# sch_Camera.net
KiCad netlist of a schematic drawn in Altium Designer
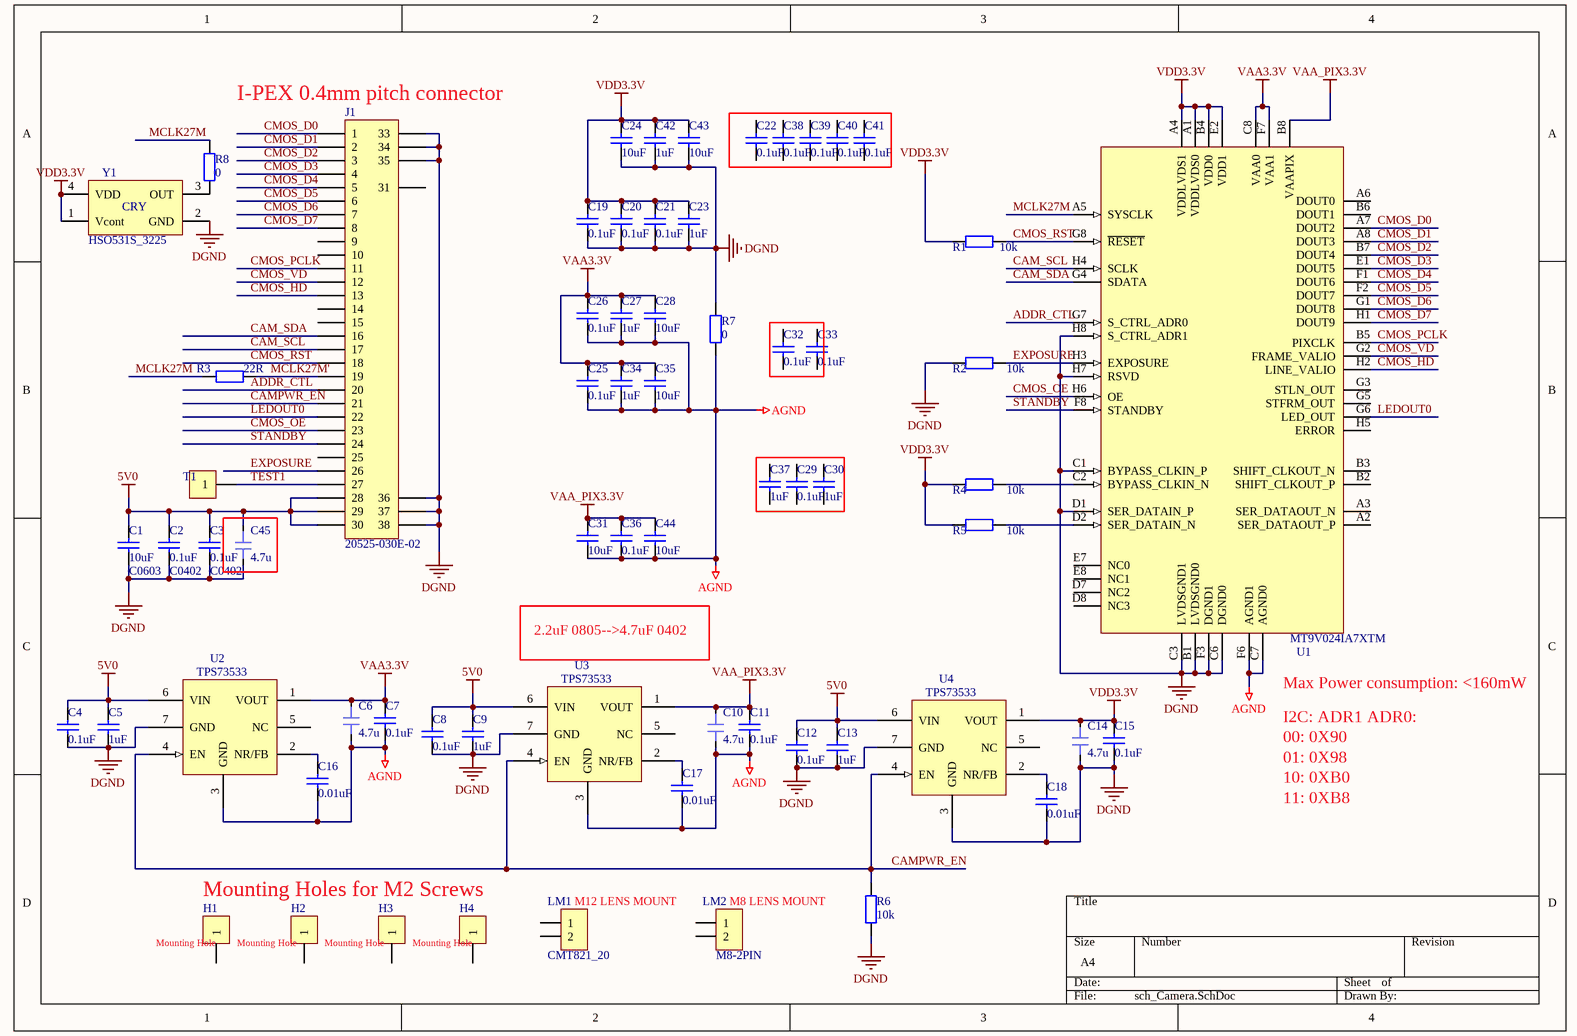
[diagram p0: sch_Camera.SchDoc]

(export (version "E")
  (design (tool "Eeschema 10.0.6"))
  (components
    (comp (ref "C1")
      (value "10uF")
      (footprint "0805C")
      (description "Capacitor")
      (fields (field (name "ALTIUM_VALUE") "C0603") (field (name "PUBLISHER") "Altium Limited"))
      (libsource (lib "Miscellaneous Devices") (part "Cap"))
    )
    (comp (ref "C2")
      (value "0.1uF")
      (footprint "0402C")
      (description "Capacitor")
      (fields (field (name "ALTIUM_VALUE") "C0402") (field (name "PUBLISHER") "Altium Limited"))
      (libsource (lib "Miscellaneous Devices") (part "Cap"))
    )
    (comp (ref "C3")
      (value "0.1uF")
      (footprint "0402C")
      (description "Capacitor")
      (fields (field (name "ALTIUM_VALUE") "C0402") (field (name "PUBLISHER") "Altium Limited"))
      (libsource (lib "Miscellaneous Devices") (part "Cap"))
    )
    (comp (ref "C4")
      (value "0.1uF")
      (footprint "0402C")
      (description "Capacitor")
      (fields (field (name "PUBLISHER") "Altium Limited"))
      (libsource (lib "Miscellaneous Devices") (part "Cap"))
    )
    (comp (ref "C5")
      (value "1uF")
      (footprint "0402C")
      (description "Capacitor")
      (fields (field (name "PUBLISHER") "Altium Limited"))
      (libsource (lib "Miscellaneous Devices") (part "Cap"))
    )
    (comp (ref "C6")
      (value "4.7u")
      (footprint "0402C")
      (description "CC0402MRX5R5BB475")
      (libsource (lib "V0P1") (part "cap0402"))
    )
    (comp (ref "C7")
      (value "0.1uF")
      (footprint "0402C")
      (description "Capacitor")
      (fields (field (name "PUBLISHER") "Altium Limited"))
      (libsource (lib "Miscellaneous Devices") (part "Cap"))
    )
    (comp (ref "C8")
      (value "0.1uF")
      (footprint "0402C")
      (description "Capacitor")
      (fields (field (name "PUBLISHER") "Altium Limited"))
      (libsource (lib "Miscellaneous Devices") (part "Cap"))
    )
    (comp (ref "C9")
      (value "1uF")
      (footprint "0402C")
      (description "Capacitor")
      (fields (field (name "PUBLISHER") "Altium Limited"))
      (libsource (lib "Miscellaneous Devices") (part "Cap"))
    )
    (comp (ref "C10")
      (value "4.7u")
      (footprint "0402C")
      (description "CC0402MRX5R5BB475")
      (libsource (lib "V0P1") (part "cap0402"))
    )
    (comp (ref "C11")
      (value "0.1uF")
      (footprint "0402C")
      (description "Capacitor")
      (fields (field (name "PUBLISHER") "Altium Limited"))
      (libsource (lib "Miscellaneous Devices") (part "Cap"))
    )
    (comp (ref "C12")
      (value "0.1uF")
      (footprint "0402C")
      (description "Capacitor")
      (fields (field (name "PUBLISHER") "Altium Limited"))
      (libsource (lib "Miscellaneous Devices") (part "Cap"))
    )
    (comp (ref "C13")
      (value "1uF")
      (footprint "0402C")
      (description "Capacitor")
      (fields (field (name "PUBLISHER") "Altium Limited"))
      (libsource (lib "Miscellaneous Devices") (part "Cap"))
    )
    (comp (ref "C14")
      (value "4.7u")
      (footprint "0402C")
      (description "CC0402MRX5R5BB475")
      (libsource (lib "V0P1") (part "cap0402"))
    )
    (comp (ref "C15")
      (value "0.1uF")
      (footprint "0402C")
      (description "Capacitor")
      (fields (field (name "PUBLISHER") "Altium Limited"))
      (libsource (lib "Miscellaneous Devices") (part "Cap"))
    )
    (comp (ref "C16")
      (value "0.01uF")
      (footprint "0402C")
      (description "Capacitor")
      (fields (field (name "PUBLISHER") "Altium Limited"))
      (libsource (lib "Miscellaneous Devices") (part "Cap"))
    )
    (comp (ref "C17")
      (value "0.01uF")
      (footprint "0402C")
      (description "Capacitor")
      (fields (field (name "PUBLISHER") "Altium Limited"))
      (libsource (lib "Miscellaneous Devices") (part "Cap"))
    )
    (comp (ref "C18")
      (value "0.01uF")
      (footprint "0402C")
      (description "Capacitor")
      (fields (field (name "PUBLISHER") "Altium Limited"))
      (libsource (lib "Miscellaneous Devices") (part "Cap"))
    )
    (comp (ref "C19")
      (value "0.1uF")
      (footprint "0402C")
      (description "Capacitor")
      (fields (field (name "PUBLISHER") "Altium Limited"))
      (libsource (lib "Miscellaneous Devices") (part "Cap"))
    )
    (comp (ref "C20")
      (value "0.1uF")
      (footprint "0402C")
      (description "Capacitor")
      (fields (field (name "PUBLISHER") "Altium Limited"))
      (libsource (lib "Miscellaneous Devices") (part "Cap"))
    )
    (comp (ref "C21")
      (value "0.1uF")
      (footprint "0402C")
      (description "Capacitor")
      (fields (field (name "PUBLISHER") "Altium Limited"))
      (libsource (lib "Miscellaneous Devices") (part "Cap"))
    )
    (comp (ref "C22")
      (value "0.1uF")
      (footprint "0402C")
      (description "Capacitor")
      (fields (field (name "PUBLISHER") "Altium Limited"))
      (libsource (lib "Miscellaneous Devices") (part "Cap"))
    )
    (comp (ref "C23")
      (value "1uF")
      (footprint "0402C")
      (description "Capacitor")
      (fields (field (name "PUBLISHER") "Altium Limited"))
      (libsource (lib "Miscellaneous Devices") (part "Cap"))
    )
    (comp (ref "C24")
      (value "10uF")
      (footprint "0805C")
      (description "Capacitor")
      (fields (field (name "PUBLISHER") "Altium Limited"))
      (libsource (lib "Miscellaneous Devices") (part "Cap"))
    )
    (comp (ref "C25")
      (value "0.1uF")
      (footprint "0402C")
      (description "Capacitor")
      (fields (field (name "PUBLISHER") "Altium Limited"))
      (libsource (lib "Miscellaneous Devices") (part "Cap"))
    )
    (comp (ref "C26")
      (value "0.1uF")
      (footprint "0402C")
      (description "Capacitor")
      (fields (field (name "PUBLISHER") "Altium Limited"))
      (libsource (lib "Miscellaneous Devices") (part "Cap"))
    )
    (comp (ref "C27")
      (value "1uF")
      (footprint "0402C")
      (description "Capacitor")
      (fields (field (name "PUBLISHER") "Altium Limited"))
      (libsource (lib "Miscellaneous Devices") (part "Cap"))
    )
    (comp (ref "C28")
      (value "10uF")
      (footprint "0805C")
      (description "Capacitor")
      (fields (field (name "PUBLISHER") "Altium Limited"))
      (libsource (lib "Miscellaneous Devices") (part "Cap"))
    )
    (comp (ref "C29")
      (value "0.1uF")
      (footprint "0402C")
      (description "Capacitor")
      (fields (field (name "PUBLISHER") "Altium Limited"))
      (libsource (lib "Miscellaneous Devices") (part "Cap"))
    )
    (comp (ref "C30")
      (value "1uF")
      (footprint "0402C")
      (description "Capacitor")
      (fields (field (name "PUBLISHER") "Altium Limited"))
      (libsource (lib "Miscellaneous Devices") (part "Cap"))
    )
    (comp (ref "C31")
      (value "10uF")
      (footprint "0805C")
      (description "Capacitor")
      (fields (field (name "PUBLISHER") "Altium Limited"))
      (libsource (lib "Miscellaneous Devices") (part "Cap"))
    )
    (comp (ref "C32")
      (value "0.1uF")
      (footprint "0402C")
      (description "Capacitor")
      (fields (field (name "PUBLISHER") "Altium Limited"))
      (libsource (lib "Miscellaneous Devices") (part "Cap"))
    )
    (comp (ref "C33")
      (value "0.1uF")
      (footprint "0402C")
      (description "Capacitor")
      (fields (field (name "PUBLISHER") "Altium Limited"))
      (libsource (lib "Miscellaneous Devices") (part "Cap"))
    )
    (comp (ref "C34")
      (value "1uF")
      (footprint "0402C")
      (description "Capacitor")
      (fields (field (name "PUBLISHER") "Altium Limited"))
      (libsource (lib "Miscellaneous Devices") (part "Cap"))
    )
    (comp (ref "C35")
      (value "10uF")
      (footprint "0805C")
      (description "Capacitor")
      (fields (field (name "PUBLISHER") "Altium Limited"))
      (libsource (lib "Miscellaneous Devices") (part "Cap"))
    )
    (comp (ref "C36")
      (value "0.1uF")
      (footprint "0402C")
      (description "Capacitor")
      (fields (field (name "PUBLISHER") "Altium Limited"))
      (libsource (lib "Miscellaneous Devices") (part "Cap"))
    )
    (comp (ref "C37")
      (value "1uF")
      (footprint "0402C")
      (description "Capacitor")
      (fields (field (name "PUBLISHER") "Altium Limited"))
      (libsource (lib "Miscellaneous Devices") (part "Cap"))
    )
    (comp (ref "C38")
      (value "0.1uF")
      (footprint "0402C")
      (description "Capacitor")
      (fields (field (name "PUBLISHER") "Altium Limited"))
      (libsource (lib "Miscellaneous Devices") (part "Cap"))
    )
    (comp (ref "C39")
      (value "0.1uF")
      (footprint "0402C")
      (description "Capacitor")
      (fields (field (name "PUBLISHER") "Altium Limited"))
      (libsource (lib "Miscellaneous Devices") (part "Cap"))
    )
    (comp (ref "C40")
      (value "0.1uF")
      (footprint "0402C")
      (description "Capacitor")
      (fields (field (name "PUBLISHER") "Altium Limited"))
      (libsource (lib "Miscellaneous Devices") (part "Cap"))
    )
    (comp (ref "C41")
      (value "0.1uF")
      (footprint "0402C")
      (description "Capacitor")
      (fields (field (name "PUBLISHER") "Altium Limited"))
      (libsource (lib "Miscellaneous Devices") (part "Cap"))
    )
    (comp (ref "C42")
      (value "1uF")
      (footprint "0402C")
      (description "Capacitor")
      (fields (field (name "PUBLISHER") "Altium Limited"))
      (libsource (lib "Miscellaneous Devices") (part "Cap"))
    )
    (comp (ref "C43")
      (value "10uF")
      (footprint "0805C")
      (description "Capacitor")
      (fields (field (name "PUBLISHER") "Altium Limited"))
      (libsource (lib "Miscellaneous Devices") (part "Cap"))
    )
    (comp (ref "C44")
      (value "10uF")
      (footprint "0805C")
      (description "Capacitor")
      (fields (field (name "PUBLISHER") "Altium Limited"))
      (libsource (lib "Miscellaneous Devices") (part "Cap"))
    )
    (comp (ref "C45")
      (value "4.7u")
      (footprint "0402C")
      (description "CC0402MRX5R5BB475")
      (libsource (lib "V0P1") (part "cap0402"))
    )
    (comp (ref "H1")
      (value "CON1")
      (footprint "PAD_M3_D350_450")
      (description "Connector")
      (libsource (lib "") (part "CON1_1"))
    )
    (comp (ref "H2")
      (value "CON1")
      (footprint "PAD_M3_D350_450")
      (description "Connector")
      (libsource (lib "") (part "CON1_1"))
    )
    (comp (ref "H3")
      (value "CON1")
      (footprint "PAD_M3_D350_450")
      (description "Connector")
      (libsource (lib "") (part "CON1_1"))
    )
    (comp (ref "H4")
      (value "CON1")
      (footprint "PAD_M3_D350_450")
      (description "Connector")
      (libsource (lib "") (part "CON1_1"))
    )
    (comp (ref "J1")
      (value "20525-030E-02")
      (footprint "HSA30_P40L196W42H10_20525")
      (libsource (lib "SZG") (part "20525-030E-02"))
    )
    (comp (ref "LM1")
      (value "CMT821_20")
      (footprint "PAD_M3_D350_450")
      (description "Connector")
      (libsource (lib "SuperSchLib") (part "CON2"))
    )
    (comp (ref "LM2")
      (value "M8-2PIN")
      (footprint "PAD_M3_D350_450")
      (description "Connector")
      (libsource (lib "SuperSchLib") (part "CON2"))
    )
    (comp (ref "R1")
      (value "10k")
      (footprint "0402R")
      (description "Resistor")
      (fields (field (name "Comment") "10K") (field (name "PUBLISHER") "Altium Limited"))
      (libsource (lib "SZG") (part "Resistor"))
    )
    (comp (ref "R2")
      (value "10k")
      (footprint "0402R")
      (description "Resistor")
      (fields (field (name "Comment") "10K") (field (name "PUBLISHER") "Altium Limited"))
      (libsource (lib "SZG") (part "Resistor"))
    )
    (comp (ref "R3")
      (value "22R")
      (footprint "0402R")
      (description "Resistor")
      (fields (field (name "PUBLISHER") "Altium Limited"))
      (libsource (lib "") (part "Resistor_2"))
    )
    (comp (ref "R4")
      (value "10k")
      (footprint "0402R")
      (description "Resistor")
      (fields (field (name "Comment") "10K") (field (name "PUBLISHER") "Altium Limited"))
      (libsource (lib "SZG") (part "Resistor"))
    )
    (comp (ref "R5")
      (value "10k")
      (footprint "0402R")
      (description "Resistor")
      (fields (field (name "Comment") "10K") (field (name "PUBLISHER") "Altium Limited"))
      (libsource (lib "SZG") (part "Resistor"))
    )
    (comp (ref "R6")
      (value "10k")
      (footprint "0402R")
      (description "Resistor")
      (fields (field (name "Comment") "10K") (field (name "PUBLISHER") "Altium Limited"))
      (libsource (lib "") (part "Resistor_3"))
    )
    (comp (ref "R7")
      (value "0")
      (footprint "0402R")
      (description "Resistor")
      (fields (field (name "Comment") "0R") (field (name "PUBLISHER") "Altium Limited"))
      (libsource (lib "") (part "Resistor_1"))
    )
    (comp (ref "R8")
      (value "0")
      (footprint "0402R")
      (description "Resistor")
      (fields (field (name "Comment") "0R") (field (name "PUBLISHER") "Altium Limited"))
      (libsource (lib "") (part "Resistor_1"))
    )
    (comp (ref "T1")
      (value "CON1")
      (footprint "PAD_TP_D1.2")
      (description "Connector")
      (libsource (lib "SuperSchLib") (part "CON1"))
    )
    (comp (ref "U1")
      (value "MT9V024IA7XTM")
      (footprint "IBGA52_8X8_P100L90W90H90R")
      (libsource (lib "SZG") (part "MT9V024IA7XTM"))
    )
    (comp (ref "U2")
      (value "TPS73533")
      (footprint "QFN8_P65L30W30H10_DRB")
      (libsource (lib "SZG") (part "TPS73533"))
    )
    (comp (ref "U3")
      (value "TPS73533")
      (footprint "QFN8_P65L30W30H10_DRB")
      (libsource (lib "SZG") (part "TPS73533"))
    )
    (comp (ref "U4")
      (value "TPS73533")
      (footprint "QFN8_P65L30W30H10_DRB")
      (libsource (lib "SZG") (part "TPS73533"))
    )
    (comp (ref "Y1")
      (value "HSO531S_3225")
      (footprint "XTAL_3225")
      (description "有源晶振")
      (libsource (lib "超集元件库") (part "CRY"))
    )
  )
  (nets
    (net (code "1") (name "/ADDR_CTL") (class "Default")
      (node (ref "J1") (pin "20") (pinfunction "20_20") (pintype "passive"))
      (node (ref "U1") (pin "G7") (pinfunction "S_CTRL_ADR0_G7") (pintype "input"))
    )
    (net (code "2") (name "/CAMPWR_EN") (class "Default")
      (node (ref "J1") (pin "21") (pinfunction "21_21") (pintype "passive"))
      (node (ref "R6") (pin "2") (pinfunction "2_2") (pintype "passive"))
      (node (ref "U2") (pin "4") (pinfunction "EN_4") (pintype "input"))
      (node (ref "U3") (pin "4") (pinfunction "EN_4") (pintype "input"))
      (node (ref "U4") (pin "4") (pinfunction "EN_4") (pintype "input"))
    )
    (net (code "3") (name "/CAM_SCL") (class "Default")
      (node (ref "J1") (pin "17") (pinfunction "17_17") (pintype "passive"))
      (node (ref "U1") (pin "H4") (pinfunction "SCLK_H4") (pintype "input"))
    )
    (net (code "4") (name "/CAM_SDA") (class "Default")
      (node (ref "J1") (pin "16") (pinfunction "16_16") (pintype "passive"))
      (node (ref "U1") (pin "G4") (pinfunction "SDATA_G4") (pintype "passive"))
    )
    (net (code "5") (name "/CMOS_D0") (class "Default")
      (node (ref "J1") (pin "1") (pinfunction "1_1") (pintype "passive"))
      (node (ref "U1") (pin "A7") (pinfunction "DOUT2_A7") (pintype "passive"))
    )
    (net (code "6") (name "/CMOS_D1") (class "Default")
      (node (ref "J1") (pin "2") (pinfunction "2_2") (pintype "passive"))
      (node (ref "U1") (pin "A8") (pinfunction "DOUT3_A8") (pintype "passive"))
    )
    (net (code "7") (name "/CMOS_D2") (class "Default")
      (node (ref "J1") (pin "3") (pinfunction "3_3") (pintype "passive"))
      (node (ref "U1") (pin "B7") (pinfunction "DOUT4_B7") (pintype "passive"))
    )
    (net (code "8") (name "/CMOS_D3") (class "Default")
      (node (ref "J1") (pin "4") (pinfunction "4_4") (pintype "passive"))
      (node (ref "U1") (pin "E1") (pinfunction "DOUT5_E1") (pintype "passive"))
    )
    (net (code "9") (name "/CMOS_D4") (class "Default")
      (node (ref "J1") (pin "5") (pinfunction "5_5") (pintype "passive"))
      (node (ref "U1") (pin "F1") (pinfunction "DOUT6_F1") (pintype "passive"))
    )
    (net (code "10") (name "/CMOS_D5") (class "Default")
      (node (ref "J1") (pin "6") (pinfunction "6_6") (pintype "passive"))
      (node (ref "U1") (pin "F2") (pinfunction "DOUT7_F2") (pintype "passive"))
    )
    (net (code "11") (name "/CMOS_D6") (class "Default")
      (node (ref "J1") (pin "7") (pinfunction "7_7") (pintype "passive"))
      (node (ref "U1") (pin "G1") (pinfunction "DOUT8_G1") (pintype "passive"))
    )
    (net (code "12") (name "/CMOS_D7") (class "Default")
      (node (ref "J1") (pin "8") (pinfunction "8_8") (pintype "passive"))
      (node (ref "U1") (pin "H1") (pinfunction "DOUT9_H1") (pintype "passive"))
    )
    (net (code "13") (name "/CMOS_HD") (class "Default")
      (node (ref "J1") (pin "13") (pinfunction "13_13") (pintype "passive"))
      (node (ref "U1") (pin "H2") (pinfunction "LINE_VALIO_H2") (pintype "passive"))
    )
    (net (code "14") (name "/CMOS_OE") (class "Default")
      (node (ref "J1") (pin "23") (pinfunction "23_23") (pintype "passive"))
      (node (ref "U1") (pin "H6") (pinfunction "OE_H6") (pintype "input"))
    )
    (net (code "15") (name "/CMOS_PCLK") (class "Default")
      (node (ref "J1") (pin "11") (pinfunction "11_11") (pintype "passive"))
      (node (ref "U1") (pin "B5") (pinfunction "PIXCLK_B5") (pintype "passive"))
    )
    (net (code "16") (name "/CMOS_RST") (class "Default")
      (node (ref "J1") (pin "18") (pinfunction "18_18") (pintype "passive"))
      (node (ref "R1") (pin "1") (pinfunction "1_1") (pintype "passive"))
      (node (ref "U1") (pin "G8") (pinfunction "~{RESET}_G8") (pintype "input"))
    )
    (net (code "17") (name "/CMOS_VD") (class "Default")
      (node (ref "J1") (pin "12") (pinfunction "12_12") (pintype "passive"))
      (node (ref "U1") (pin "G2") (pinfunction "FRAME_VALIO_G2") (pintype "passive"))
    )
    (net (code "18") (name "/EXPOSURE") (class "Default")
      (node (ref "J1") (pin "26") (pinfunction "26_26") (pintype "passive"))
      (node (ref "R2") (pin "1") (pinfunction "1_1") (pintype "passive"))
      (node (ref "U1") (pin "H3") (pinfunction "EXPOSURE_H3") (pintype "input"))
    )
    (net (code "19") (name "/LEDOUT0") (class "Default")
      (node (ref "J1") (pin "22") (pinfunction "22_22") (pintype "passive"))
      (node (ref "U1") (pin "G6") (pinfunction "LED_OUT_G6") (pintype "passive"))
    )
    (net (code "20") (name "/MCLK27M") (class "Default")
      (node (ref "R3") (pin "1") (pinfunction "1_1") (pintype "passive"))
      (node (ref "R8") (pin "1") (pinfunction "1_1") (pintype "passive"))
      (node (ref "U1") (pin "A5") (pinfunction "SYSCLK_A5") (pintype "input"))
    )
    (net (code "21") (name "/MCLK27M'") (class "Default")
      (node (ref "J1") (pin "19") (pinfunction "19_19") (pintype "passive"))
      (node (ref "R3") (pin "2") (pinfunction "2_2") (pintype "passive"))
    )
    (net (code "22") (name "/STANDBY") (class "Default")
      (node (ref "J1") (pin "24") (pinfunction "24_24") (pintype "passive"))
      (node (ref "U1") (pin "F8") (pinfunction "STANDBY_F8") (pintype "input"))
    )
    (net (code "23") (name "/TEST1") (class "Default")
      (node (ref "J1") (pin "27") (pinfunction "27_27") (pintype "passive"))
      (node (ref "T1") (pin "1") (pinfunction "1_1") (pintype "passive"))
    )
    (net (code "24") (name "5V0") (class "Default")
      (node (ref "C1") (pin "2") (pinfunction "2_2") (pintype "passive"))
      (node (ref "C12") (pin "2") (pinfunction "2_2") (pintype "passive"))
      (node (ref "C13") (pin "2") (pinfunction "2_2") (pintype "passive"))
      (node (ref "C2") (pin "2") (pinfunction "2_2") (pintype "passive"))
      (node (ref "C3") (pin "2") (pinfunction "2_2") (pintype "passive"))
      (node (ref "C4") (pin "2") (pinfunction "2_2") (pintype "passive"))
      (node (ref "C45") (pin "1") (pinfunction "1_1") (pintype "passive"))
      (node (ref "C5") (pin "2") (pinfunction "2_2") (pintype "passive"))
      (node (ref "C8") (pin "2") (pinfunction "2_2") (pintype "passive"))
      (node (ref "C9") (pin "2") (pinfunction "2_2") (pintype "passive"))
      (node (ref "J1") (pin "28") (pinfunction "28_28") (pintype "passive"))
      (node (ref "J1") (pin "29") (pinfunction "29_29") (pintype "passive"))
      (node (ref "J1") (pin "30") (pinfunction "30_30") (pintype "passive"))
      (node (ref "U2") (pin "6") (pinfunction "VIN_6") (pintype "passive"))
      (node (ref "U3") (pin "6") (pinfunction "VIN_6") (pintype "passive"))
      (node (ref "U4") (pin "6") (pinfunction "VIN_6") (pintype "passive"))
    )
    (net (code "25") (name "AGND") (class "Default")
      (node (ref "C10") (pin "2") (pinfunction "2_2") (pintype "passive"))
      (node (ref "C11") (pin "1") (pinfunction "1_1") (pintype "passive"))
      (node (ref "C16") (pin "1") (pinfunction "1_1") (pintype "passive"))
      (node (ref "C17") (pin "1") (pinfunction "1_1") (pintype "passive"))
      (node (ref "C25") (pin "1") (pinfunction "1_1") (pintype "passive"))
      (node (ref "C26") (pin "1") (pinfunction "1_1") (pintype "passive"))
      (node (ref "C27") (pin "1") (pinfunction "1_1") (pintype "passive"))
      (node (ref "C28") (pin "1") (pinfunction "1_1") (pintype "passive"))
      (node (ref "C31") (pin "1") (pinfunction "1_1") (pintype "passive"))
      (node (ref "C34") (pin "1") (pinfunction "1_1") (pintype "passive"))
      (node (ref "C35") (pin "1") (pinfunction "1_1") (pintype "passive"))
      (node (ref "C36") (pin "1") (pinfunction "1_1") (pintype "passive"))
      (node (ref "C44") (pin "1") (pinfunction "1_1") (pintype "passive"))
      (node (ref "C6") (pin "2") (pinfunction "2_2") (pintype "passive"))
      (node (ref "C7") (pin "1") (pinfunction "1_1") (pintype "passive"))
      (node (ref "R7") (pin "2") (pinfunction "2_2") (pintype "passive"))
      (node (ref "U1") (pin "C7") (pinfunction "AGND0_C7") (pintype "power_in"))
      (node (ref "U1") (pin "F6") (pinfunction "AGND1_F6") (pintype "power_in"))
      (node (ref "U2") (pin "3") (pinfunction "GND_3") (pintype "passive"))
      (node (ref "U3") (pin "3") (pinfunction "GND_3") (pintype "passive"))
    )
    (net (code "26") (name "DGND") (class "Default")
      (node (ref "C1") (pin "1") (pinfunction "1_1") (pintype "passive"))
      (node (ref "C12") (pin "1") (pinfunction "1_1") (pintype "passive"))
      (node (ref "C13") (pin "1") (pinfunction "1_1") (pintype "passive"))
      (node (ref "C14") (pin "2") (pinfunction "2_2") (pintype "passive"))
      (node (ref "C15") (pin "1") (pinfunction "1_1") (pintype "passive"))
      (node (ref "C18") (pin "1") (pinfunction "1_1") (pintype "passive"))
      (node (ref "C19") (pin "1") (pinfunction "1_1") (pintype "passive"))
      (node (ref "C2") (pin "1") (pinfunction "1_1") (pintype "passive"))
      (node (ref "C20") (pin "1") (pinfunction "1_1") (pintype "passive"))
      (node (ref "C21") (pin "1") (pinfunction "1_1") (pintype "passive"))
      (node (ref "C23") (pin "1") (pinfunction "1_1") (pintype "passive"))
      (node (ref "C24") (pin "1") (pinfunction "1_1") (pintype "passive"))
      (node (ref "C3") (pin "1") (pinfunction "1_1") (pintype "passive"))
      (node (ref "C4") (pin "1") (pinfunction "1_1") (pintype "passive"))
      (node (ref "C42") (pin "1") (pinfunction "1_1") (pintype "passive"))
      (node (ref "C43") (pin "1") (pinfunction "1_1") (pintype "passive"))
      (node (ref "C45") (pin "2") (pinfunction "2_2") (pintype "passive"))
      (node (ref "C5") (pin "1") (pinfunction "1_1") (pintype "passive"))
      (node (ref "C8") (pin "1") (pinfunction "1_1") (pintype "passive"))
      (node (ref "C9") (pin "1") (pinfunction "1_1") (pintype "passive"))
      (node (ref "J1") (pin "33") (pinfunction "33_33") (pintype "passive"))
      (node (ref "J1") (pin "34") (pinfunction "34_34") (pintype "passive"))
      (node (ref "J1") (pin "35") (pinfunction "35_35") (pintype "passive"))
      (node (ref "J1") (pin "36") (pinfunction "36_36") (pintype "passive"))
      (node (ref "J1") (pin "37") (pinfunction "37_37") (pintype "passive"))
      (node (ref "J1") (pin "38") (pinfunction "38_38") (pintype "passive"))
      (node (ref "R2") (pin "2") (pinfunction "2_2") (pintype "passive"))
      (node (ref "R6") (pin "1") (pinfunction "1_1") (pintype "passive"))
      (node (ref "R7") (pin "1") (pinfunction "1_1") (pintype "passive"))
      (node (ref "U1") (pin "B1") (pinfunction "LVDSGND0_B1") (pintype "power_in"))
      (node (ref "U1") (pin "C1") (pinfunction "BYPASS_CLKIN_P_C1") (pintype "input"))
      (node (ref "U1") (pin "C3") (pinfunction "LVDSGND1_C3") (pintype "power_in"))
      (node (ref "U1") (pin "C6") (pinfunction "DGND0_C6") (pintype "power_in"))
      (node (ref "U1") (pin "D1") (pinfunction "SER_DATAIN_P_D1") (pintype "input"))
      (node (ref "U1") (pin "F3") (pinfunction "DGND1_F3") (pintype "power_in"))
      (node (ref "U1") (pin "H7") (pinfunction "RSVD_H7") (pintype "input"))
      (node (ref "U1") (pin "H8") (pinfunction "S_CTRL_ADR1_H8") (pintype "input"))
      (node (ref "U2") (pin "7") (pinfunction "GND_7") (pintype "passive"))
      (node (ref "U3") (pin "7") (pinfunction "GND_7") (pintype "passive"))
      (node (ref "U4") (pin "3") (pinfunction "GND_3") (pintype "passive"))
      (node (ref "U4") (pin "7") (pinfunction "GND_7") (pintype "passive"))
      (node (ref "Y1") (pin "2") (pinfunction "GND_2") (pintype "passive"))
    )
    (net (code "27") (name "Net-(U1-BYPASS_CLKIN_N)") (class "Default")
      (node (ref "R4") (pin "1") (pinfunction "1_1") (pintype "passive"))
      (node (ref "U1") (pin "C2") (pinfunction "BYPASS_CLKIN_N_C2") (pintype "input"))
    )
    (net (code "28") (name "Net-(U1-SER_DATAIN_N)") (class "Default")
      (node (ref "R5") (pin "1") (pinfunction "1_1") (pintype "passive"))
      (node (ref "U1") (pin "D2") (pinfunction "SER_DATAIN_N_D2") (pintype "input"))
    )
    (net (code "29") (name "Net-(U2-NR{slash}FB)") (class "Default")
      (node (ref "C16") (pin "2") (pinfunction "2_2") (pintype "passive"))
      (node (ref "U2") (pin "2") (pinfunction "NR/FB_2") (pintype "passive"))
    )
    (net (code "30") (name "Net-(U3-NR{slash}FB)") (class "Default")
      (node (ref "C17") (pin "2") (pinfunction "2_2") (pintype "passive"))
      (node (ref "U3") (pin "2") (pinfunction "NR/FB_2") (pintype "passive"))
    )
    (net (code "31") (name "Net-(U4-NR{slash}FB)") (class "Default")
      (node (ref "C18") (pin "2") (pinfunction "2_2") (pintype "passive"))
      (node (ref "U4") (pin "2") (pinfunction "NR/FB_2") (pintype "passive"))
    )
    (net (code "32") (name "Net-(Y1-OUT)") (class "Default")
      (node (ref "R8") (pin "2") (pinfunction "2_2") (pintype "passive"))
      (node (ref "Y1") (pin "3") (pinfunction "OUT_3") (pintype "passive"))
    )
    (net (code "33") (name "VAA3.3V") (class "Default")
      (node (ref "C25") (pin "2") (pinfunction "2_2") (pintype "passive"))
      (node (ref "C26") (pin "2") (pinfunction "2_2") (pintype "passive"))
      (node (ref "C27") (pin "2") (pinfunction "2_2") (pintype "passive"))
      (node (ref "C28") (pin "2") (pinfunction "2_2") (pintype "passive"))
      (node (ref "C34") (pin "2") (pinfunction "2_2") (pintype "passive"))
      (node (ref "C35") (pin "2") (pinfunction "2_2") (pintype "passive"))
      (node (ref "C6") (pin "1") (pinfunction "1_1") (pintype "passive"))
      (node (ref "C7") (pin "2") (pinfunction "2_2") (pintype "passive"))
      (node (ref "U1") (pin "C8") (pinfunction "VAA0_C8") (pintype "power_in"))
      (node (ref "U1") (pin "F7") (pinfunction "VAA1_F7") (pintype "power_in"))
      (node (ref "U2") (pin "1") (pinfunction "VOUT_1") (pintype "passive"))
    )
    (net (code "34") (name "VAA_PIX3.3V") (class "Default")
      (node (ref "C10") (pin "1") (pinfunction "1_1") (pintype "passive"))
      (node (ref "C11") (pin "2") (pinfunction "2_2") (pintype "passive"))
      (node (ref "C31") (pin "2") (pinfunction "2_2") (pintype "passive"))
      (node (ref "C36") (pin "2") (pinfunction "2_2") (pintype "passive"))
      (node (ref "C44") (pin "2") (pinfunction "2_2") (pintype "passive"))
      (node (ref "U1") (pin "B8") (pinfunction "VAAPIX_B8") (pintype "power_in"))
      (node (ref "U3") (pin "1") (pinfunction "VOUT_1") (pintype "passive"))
    )
    (net (code "35") (name "VDD3.3V") (class "Default")
      (node (ref "C14") (pin "1") (pinfunction "1_1") (pintype "passive"))
      (node (ref "C15") (pin "2") (pinfunction "2_2") (pintype "passive"))
      (node (ref "C19") (pin "2") (pinfunction "2_2") (pintype "passive"))
      (node (ref "C20") (pin "2") (pinfunction "2_2") (pintype "passive"))
      (node (ref "C21") (pin "2") (pinfunction "2_2") (pintype "passive"))
      (node (ref "C23") (pin "2") (pinfunction "2_2") (pintype "passive"))
      (node (ref "C24") (pin "2") (pinfunction "2_2") (pintype "passive"))
      (node (ref "C42") (pin "2") (pinfunction "2_2") (pintype "passive"))
      (node (ref "C43") (pin "2") (pinfunction "2_2") (pintype "passive"))
      (node (ref "R1") (pin "2") (pinfunction "2_2") (pintype "passive"))
      (node (ref "R4") (pin "2") (pinfunction "2_2") (pintype "passive"))
      (node (ref "R5") (pin "2") (pinfunction "2_2") (pintype "passive"))
      (node (ref "U1") (pin "A1") (pinfunction "VDDLVDS0_A1") (pintype "power_in"))
      (node (ref "U1") (pin "A4") (pinfunction "VDDLVDS1_A4") (pintype "power_in"))
      (node (ref "U1") (pin "B4") (pinfunction "VDD0_B4") (pintype "power_in"))
      (node (ref "U1") (pin "E2") (pinfunction "VDD1_E2") (pintype "power_in"))
      (node (ref "U4") (pin "1") (pinfunction "VOUT_1") (pintype "passive"))
      (node (ref "Y1") (pin "1") (pinfunction "Vcont_1") (pintype "passive"))
      (node (ref "Y1") (pin "4") (pinfunction "VDD_4") (pintype "passive"))
    )
    (net (code "36") (name "unconnected-(C22-Pad1)") (class "Default")
      (node (ref "C22") (pin "1") (pinfunction "1_1") (pintype "passive"))
    )
    (net (code "37") (name "unconnected-(C22-Pad2)") (class "Default")
      (node (ref "C22") (pin "2") (pinfunction "2_2") (pintype "passive"))
    )
    (net (code "38") (name "unconnected-(C29-Pad1)") (class "Default")
      (node (ref "C29") (pin "1") (pinfunction "1_1") (pintype "passive"))
    )
    (net (code "39") (name "unconnected-(C29-Pad2)") (class "Default")
      (node (ref "C29") (pin "2") (pinfunction "2_2") (pintype "passive"))
    )
    (net (code "40") (name "unconnected-(C30-Pad1)") (class "Default")
      (node (ref "C30") (pin "1") (pinfunction "1_1") (pintype "passive"))
    )
    (net (code "41") (name "unconnected-(C30-Pad2)") (class "Default")
      (node (ref "C30") (pin "2") (pinfunction "2_2") (pintype "passive"))
    )
    (net (code "42") (name "unconnected-(C32-Pad1)") (class "Default")
      (node (ref "C32") (pin "1") (pinfunction "1_1") (pintype "passive"))
    )
    (net (code "43") (name "unconnected-(C32-Pad2)") (class "Default")
      (node (ref "C32") (pin "2") (pinfunction "2_2") (pintype "passive"))
    )
    (net (code "44") (name "unconnected-(C33-Pad1)") (class "Default")
      (node (ref "C33") (pin "1") (pinfunction "1_1") (pintype "passive"))
    )
    (net (code "45") (name "unconnected-(C33-Pad2)") (class "Default")
      (node (ref "C33") (pin "2") (pinfunction "2_2") (pintype "passive"))
    )
    (net (code "46") (name "unconnected-(C37-Pad1)") (class "Default")
      (node (ref "C37") (pin "1") (pinfunction "1_1") (pintype "passive"))
    )
    (net (code "47") (name "unconnected-(C37-Pad2)") (class "Default")
      (node (ref "C37") (pin "2") (pinfunction "2_2") (pintype "passive"))
    )
    (net (code "48") (name "unconnected-(C38-Pad1)") (class "Default")
      (node (ref "C38") (pin "1") (pinfunction "1_1") (pintype "passive"))
    )
    (net (code "49") (name "unconnected-(C38-Pad2)") (class "Default")
      (node (ref "C38") (pin "2") (pinfunction "2_2") (pintype "passive"))
    )
    (net (code "50") (name "unconnected-(C39-Pad1)") (class "Default")
      (node (ref "C39") (pin "1") (pinfunction "1_1") (pintype "passive"))
    )
    (net (code "51") (name "unconnected-(C39-Pad2)") (class "Default")
      (node (ref "C39") (pin "2") (pinfunction "2_2") (pintype "passive"))
    )
    (net (code "52") (name "unconnected-(C40-Pad1)") (class "Default")
      (node (ref "C40") (pin "1") (pinfunction "1_1") (pintype "passive"))
    )
    (net (code "53") (name "unconnected-(C40-Pad2)") (class "Default")
      (node (ref "C40") (pin "2") (pinfunction "2_2") (pintype "passive"))
    )
    (net (code "54") (name "unconnected-(C41-Pad1)") (class "Default")
      (node (ref "C41") (pin "1") (pinfunction "1_1") (pintype "passive"))
    )
    (net (code "55") (name "unconnected-(C41-Pad2)") (class "Default")
      (node (ref "C41") (pin "2") (pinfunction "2_2") (pintype "passive"))
    )
    (net (code "56") (name "unconnected-(H1-Pad1)") (class "Default")
      (node (ref "H1") (pin "1") (pinfunction "1_1") (pintype "passive"))
    )
    (net (code "57") (name "unconnected-(H2-Pad1)") (class "Default")
      (node (ref "H2") (pin "1") (pinfunction "1_1") (pintype "passive"))
    )
    (net (code "58") (name "unconnected-(H3-Pad1)") (class "Default")
      (node (ref "H3") (pin "1") (pinfunction "1_1") (pintype "passive"))
    )
    (net (code "59") (name "unconnected-(H4-Pad1)") (class "Default")
      (node (ref "H4") (pin "1") (pinfunction "1_1") (pintype "passive"))
    )
    (net (code "60") (name "unconnected-(J1-Pad9)") (class "Default")
      (node (ref "J1") (pin "9") (pinfunction "9_9") (pintype "passive"))
    )
    (net (code "61") (name "unconnected-(J1-Pad10)") (class "Default")
      (node (ref "J1") (pin "10") (pinfunction "10_10") (pintype "passive"))
    )
    (net (code "62") (name "unconnected-(J1-Pad14)") (class "Default")
      (node (ref "J1") (pin "14") (pinfunction "14_14") (pintype "passive"))
    )
    (net (code "63") (name "unconnected-(J1-Pad15)") (class "Default")
      (node (ref "J1") (pin "15") (pinfunction "15_15") (pintype "passive"))
    )
    (net (code "64") (name "unconnected-(J1-Pad25)") (class "Default")
      (node (ref "J1") (pin "25") (pinfunction "25_25") (pintype "passive"))
    )
    (net (code "65") (name "unconnected-(J1-Pad31)") (class "Default")
      (node (ref "J1") (pin "31") (pinfunction "31_31") (pintype "passive"))
    )
    (net (code "66") (name "unconnected-(LM1-Pad1)") (class "Default")
      (node (ref "LM1") (pin "1") (pinfunction "1_1") (pintype "passive"))
    )
    (net (code "67") (name "unconnected-(LM1-Pad2)") (class "Default")
      (node (ref "LM1") (pin "2") (pinfunction "2_2") (pintype "passive"))
    )
    (net (code "68") (name "unconnected-(LM2-Pad1)") (class "Default")
      (node (ref "LM2") (pin "1") (pinfunction "1_1") (pintype "passive"))
    )
    (net (code "69") (name "unconnected-(LM2-Pad2)") (class "Default")
      (node (ref "LM2") (pin "2") (pinfunction "2_2") (pintype "passive"))
    )
    (net (code "70") (name "unconnected-(U1-DOUT0-PadA6)") (class "Default")
      (node (ref "U1") (pin "A6") (pinfunction "DOUT0_A6") (pintype "passive"))
    )
    (net (code "71") (name "unconnected-(U1-DOUT1-PadB6)") (class "Default")
      (node (ref "U1") (pin "B6") (pinfunction "DOUT1_B6") (pintype "passive"))
    )
    (net (code "72") (name "unconnected-(U1-ERROR-PadH5)") (class "Default")
      (node (ref "U1") (pin "H5") (pinfunction "ERROR_H5") (pintype "passive"))
    )
    (net (code "73") (name "unconnected-(U1-NC0-PadE7)") (class "Default")
      (node (ref "U1") (pin "E7") (pinfunction "NC0_E7") (pintype "passive"))
    )
    (net (code "74") (name "unconnected-(U1-NC1-PadE8)") (class "Default")
      (node (ref "U1") (pin "E8") (pinfunction "NC1_E8") (pintype "power_in"))
    )
    (net (code "75") (name "unconnected-(U1-NC2-PadD7)") (class "Default")
      (node (ref "U1") (pin "D7") (pinfunction "NC2_D7") (pintype "power_in"))
    )
    (net (code "76") (name "unconnected-(U1-NC3-PadD8)") (class "Default")
      (node (ref "U1") (pin "D8") (pinfunction "NC3_D8") (pintype "power_in"))
    )
    (net (code "77") (name "unconnected-(U1-SER_DATAOUT_N-PadA3)") (class "Default")
      (node (ref "U1") (pin "A3") (pinfunction "SER_DATAOUT_N_A3") (pintype "passive"))
    )
    (net (code "78") (name "unconnected-(U1-SER_DATAOUT_P-PadA2)") (class "Default")
      (node (ref "U1") (pin "A2") (pinfunction "SER_DATAOUT_P_A2") (pintype "passive"))
    )
    (net (code "79") (name "unconnected-(U1-SHIFT_CLKOUT_N-PadB3)") (class "Default")
      (node (ref "U1") (pin "B3") (pinfunction "SHIFT_CLKOUT_N_B3") (pintype "passive"))
    )
    (net (code "80") (name "unconnected-(U1-SHIFT_CLKOUT_P-PadB2)") (class "Default")
      (node (ref "U1") (pin "B2") (pinfunction "SHIFT_CLKOUT_P_B2") (pintype "passive"))
    )
    (net (code "81") (name "unconnected-(U1-STFRM_OUT-PadG5)") (class "Default")
      (node (ref "U1") (pin "G5") (pinfunction "STFRM_OUT_G5") (pintype "passive"))
    )
    (net (code "82") (name "unconnected-(U1-STLN_OUT-PadG3)") (class "Default")
      (node (ref "U1") (pin "G3") (pinfunction "STLN_OUT_G3") (pintype "passive"))
    )
    (net (code "83") (name "unconnected-(U2-NC-Pad5)") (class "Default")
      (node (ref "U2") (pin "5") (pinfunction "NC_5") (pintype "passive"))
    )
    (net (code "84") (name "unconnected-(U3-NC-Pad5)") (class "Default")
      (node (ref "U3") (pin "5") (pinfunction "NC_5") (pintype "passive"))
    )
    (net (code "85") (name "unconnected-(U4-NC-Pad5)") (class "Default")
      (node (ref "U4") (pin "5") (pinfunction "NC_5") (pintype "passive"))
    )
  )
)
